# STM32.net
KiCad netlist of a schematic drawn in Altium Designer
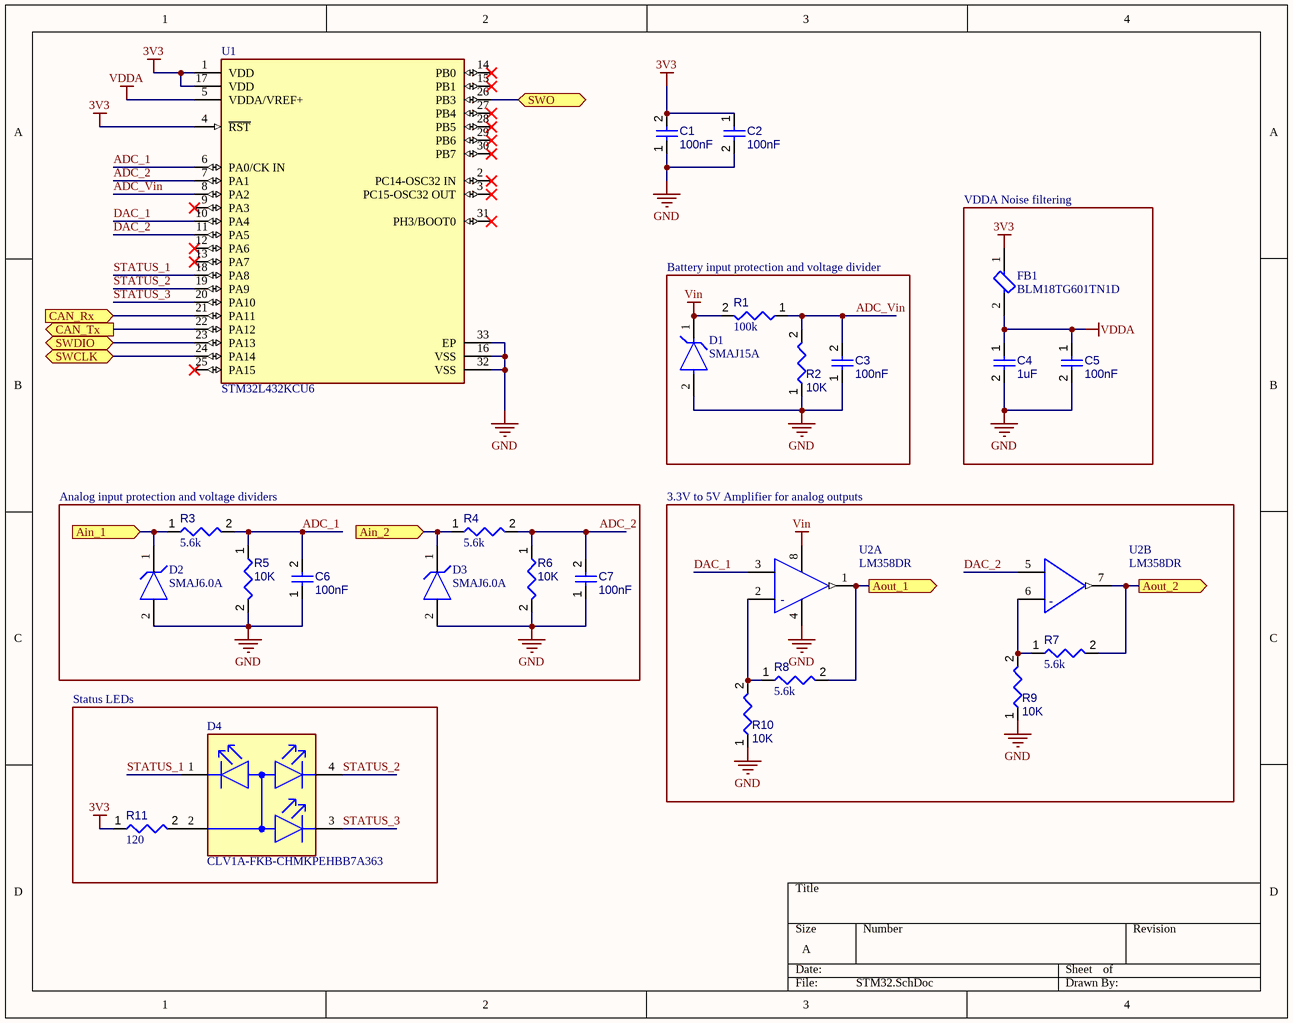
[diagram p0: STM32.SchDoc]

(export (version "E")
  (design (tool "Eeschema 10.0.6"))
  (components
    (comp (ref "C1")
      (value "100nF")
      (footprint "CAPC0402(1005)60_L")
      (description "Chip Capacitor, 100nF +/-20%, 10V, 0402, Thickness 0.6 mm")
      (fields (field (name "TOLERANCE") "20%"))
      (libsource (lib "Bronco Racing") (part "CAP-NP-2"))
    )
    (comp (ref "C2")
      (value "100nF")
      (footprint "CAPC0402(1005)60_L")
      (description "Chip Capacitor, 100nF +/-20%, 10V, 0402, Thickness 0.6 mm")
      (fields (field (name "TOLERANCE") "20%"))
      (libsource (lib "Bronco Racing") (part "CAP-NP-2"))
    )
    (comp (ref "C3")
      (value "100nF")
      (footprint "CAPC0402(1005)60_L")
      (description "Chip Capacitor, 100nF +/-20%, 10V, 0402, Thickness 0.6 mm")
      (fields (field (name "TOLERANCE") "20%"))
      (libsource (lib "Bronco Racing") (part "CAP-NP-2"))
    )
    (comp (ref "C4")
      (value "1uF")
      (footprint "CAPC0402(1005)60_L")
      (description "Chip Capacitor, 1µF +/-20%, 10V, 0402, Thickness 0.6 mm")
      (fields (field (name "TOLERANCE") "10%"))
      (libsource (lib "Bronco Racing") (part "CAP-NP-2"))
    )
    (comp (ref "C5")
      (value "100nF")
      (footprint "CAPC0402(1005)60_L")
      (description "Chip Capacitor, 100nF +/-20%, 10V, 0402, Thickness 0.6 mm")
      (fields (field (name "TOLERANCE") "20%"))
      (libsource (lib "Bronco Racing") (part "CAP-NP-2"))
    )
    (comp (ref "C6")
      (value "100nF")
      (footprint "CAPC0402(1005)60_L")
      (description "Chip Capacitor, 100nF +/-20%, 10V, 0402, Thickness 0.6 mm")
      (fields (field (name "TOLERANCE") "20%"))
      (libsource (lib "Bronco Racing") (part "CAP-NP-2"))
    )
    (comp (ref "C7")
      (value "100nF")
      (footprint "CAPC0402(1005)60_L")
      (description "Chip Capacitor, 100nF +/-20%, 10V, 0402, Thickness 0.6 mm")
      (fields (field (name "TOLERANCE") "20%"))
      (libsource (lib "Bronco Racing") (part "CAP-NP-2"))
    )
    (comp (ref "D1")
      (value "SMAJ15A")
      (footprint "FP-SMA-MFG")
      (description "TVS DIODE 15V 24.4V SMA")
      (fields
        (field (name "OCTOPART") "https://octopart.com/smaj15a-bourns-12809353")
        (field (name "MANUFACTURER") "Bourns Inc.")
      )
      (libsource (lib "Altium Content Vault") (part "f813f71cba58e380607f5dd3caf9714"))
    )
    (comp (ref "D2")
      (value "SMAJ6.0A")
      (footprint "FP-SMA-MFG")
      (description "TVS DIODE 6V 10.3V SMA")
      (fields
        (field (name "OCTOPART") "https://octopart.com/smaj6.0a-bourns-12809397")
        (field (name "MANUFACTURER") "Bourns Inc.")
      )
      (libsource (lib "Altium Content Vault") (part "673ecd2ea4d7fb87b4005b0cb348b7d"))
    )
    (comp (ref "D3")
      (value "SMAJ6.0A")
      (footprint "FP-SMA-MFG")
      (description "TVS DIODE 6V 10.3V SMA")
      (fields
        (field (name "OCTOPART") "https://octopart.com/smaj6.0a-bourns-12809397")
        (field (name "MANUFACTURER") "Bourns Inc.")
      )
      (libsource (lib "Altium Content Vault") (part "673ecd2ea4d7fb87b4005b0cb348b7d"))
    )
    (comp (ref "D4")
      (value "CLV1A-FKB-CHMKPEHBB7A363")
      (footprint "FP-CLV1A-FKB-CHMKPEHBB7A3-MFG")
      (description "LED RGB 4PLCC SMD")
      (libsource (lib "Altium Content Vault") (part "37e83e7cb408f3cd33eae76522c4c17"))
    )
    (comp (ref "FB1")
      (value "BLM18TG601TN1D")
      (footprint "FP-BLM18-0_15-0_1-t0_6-MFG")
      (description "FERRITE BEAD 600 OHM 0603 1LN")
      (fields (field (name "TOLERANCE") "25%"))
      (libsource (lib "Altium Content Vault") (part "5f30dd21d616792df468990f7003faa"))
    )
    (comp (ref "R1")
      (value "100k")
      (footprint "RESC0402(1005)_L")
      (description "Chip Resistor, 100 kOhms, +/-1 %, 63 mW, -55 to 155 degC, 0402")
      (fields (field (name "POWER") "63mW") (field (name "TOLERANCE") "1%"))
      (libsource (lib "Bronco Racing") (part "RES-2"))
    )
    (comp (ref "R2")
      (value "10K")
      (footprint "RESC0402(1005)_L")
      (description "Chip Resistor, 10 kOhms, +/-1 %, 63 mW, -55 to 125 degC, 0402")
      (fields (field (name "POWER") "63mW") (field (name "TOLERANCE") "1%"))
      (libsource (lib "Bronco Racing") (part "RES-2"))
    )
    (comp (ref "R3")
      (value "5.6k")
      (footprint "RESC0402(1005)_L")
      (description "Chip Resistor, 5,6 kOhms, +/-5 %, 63 mW, -55 to 155 degC, 0402")
      (fields (field (name "TOLERANCE") "5%") (field (name "POWER") "63mW"))
      (libsource (lib "Bronco Racing") (part "RES-2"))
    )
    (comp (ref "R4")
      (value "5.6k")
      (footprint "RESC0402(1005)_L")
      (description "Chip Resistor, 5,6 kOhms, +/-5 %, 63 mW, -55 to 155 degC, 0402")
      (fields (field (name "TOLERANCE") "5%") (field (name "POWER") "63mW"))
      (libsource (lib "Bronco Racing") (part "RES-2"))
    )
    (comp (ref "R5")
      (value "10K")
      (footprint "RESC0402(1005)_L")
      (description "Chip Resistor, 10 kOhms, +/-1 %, 63 mW, -55 to 125 degC, 0402")
      (fields (field (name "POWER") "63mW") (field (name "TOLERANCE") "1%"))
      (libsource (lib "Bronco Racing") (part "RES-2"))
    )
    (comp (ref "R6")
      (value "10K")
      (footprint "RESC0402(1005)_L")
      (description "Chip Resistor, 10 kOhms, +/-1 %, 63 mW, -55 to 125 degC, 0402")
      (fields (field (name "POWER") "63mW") (field (name "TOLERANCE") "1%"))
      (libsource (lib "Bronco Racing") (part "RES-2"))
    )
    (comp (ref "R7")
      (value "5.6k")
      (footprint "RESC0402(1005)_L")
      (description "Chip Resistor, 5,6 kOhms, +/-5 %, 63 mW, -55 to 155 degC, 0402")
      (fields (field (name "TOLERANCE") "5%") (field (name "POWER") "63mW"))
      (libsource (lib "Bronco Racing") (part "RES-2"))
    )
    (comp (ref "R8")
      (value "5.6k")
      (footprint "RESC0402(1005)_L")
      (description "Chip Resistor, 5,6 kOhms, +/-5 %, 63 mW, -55 to 155 degC, 0402")
      (fields (field (name "TOLERANCE") "5%") (field (name "POWER") "63mW"))
      (libsource (lib "Bronco Racing") (part "RES-2"))
    )
    (comp (ref "R9")
      (value "10K")
      (footprint "RESC0402(1005)_L")
      (description "Chip Resistor, 10 kOhms, +/-1 %, 63 mW, -55 to 125 degC, 0402")
      (fields (field (name "POWER") "63mW") (field (name "TOLERANCE") "1%"))
      (libsource (lib "Bronco Racing") (part "RES-2"))
    )
    (comp (ref "R10")
      (value "10K")
      (footprint "RESC0402(1005)_L")
      (description "Chip Resistor, 10 kOhms, +/-1 %, 63 mW, -55 to 125 degC, 0402")
      (fields (field (name "POWER") "63mW") (field (name "TOLERANCE") "1%"))
      (libsource (lib "Bronco Racing") (part "RES-2"))
    )
    (comp (ref "R11")
      (value "120")
      (footprint "RESC0603(1608)_L")
      (description "Chip Resistor, 120 Ohms, +/-5 %, 0.1 W, -55 to 155 degC, 0603")
      (fields (field (name "POWER") "100mW") (field (name "TOLERANCE") "5%"))
      (libsource (lib "Bronco Racing") (part "RES-2"))
    )
    (comp (ref "U1")
      (value "STM32L432KCU6")
      (footprint "FP-UFQFPN32-A0B8-MFG")
      (description "IC MCU 32BIT 256KB FLASH 32QFPN")
      (fields
        (field (name "OCTOPART") "https://octopart.com/stm32l432kcu6-stmicroelectronics-71093510")
        (field (name "MANUFACTURER") "STMicroelectronics")
      )
      (libsource (lib "Altium Content Vault") (part "f3240dca552e0aa49c1b4baba198c12"))
    )
    (comp (ref "U2")
      (value "LM358DR")
      (footprint "FP-D0008A-MFG")
      (description "IC OPAMP GP 2 CIRCUIT 8SOIC")
      (libsource (lib "Altium Content Vault") (part "0afdfe5f461d2cdd85604ff8654be97"))
    )
  )
  (nets
    (net (code "1") (name "/ADC_1") (class "Default")
      (node (ref "C6") (pin "2") (pinfunction "2_2") (pintype "passive"))
      (node (ref "R3") (pin "2") (pinfunction "2_2") (pintype "passive"))
      (node (ref "R5") (pin "1") (pinfunction "1_1") (pintype "passive"))
      (node (ref "U1") (pin "6") (pinfunction "PA0/CK_IN_6") (pintype "bidirectional"))
    )
    (net (code "2") (name "/ADC_2") (class "Default")
      (node (ref "C7") (pin "2") (pinfunction "2_2") (pintype "passive"))
      (node (ref "R4") (pin "2") (pinfunction "2_2") (pintype "passive"))
      (node (ref "R6") (pin "1") (pinfunction "1_1") (pintype "passive"))
      (node (ref "U1") (pin "7") (pinfunction "PA1_7") (pintype "bidirectional"))
    )
    (net (code "3") (name "/ADC_Vin") (class "Default")
      (node (ref "C3") (pin "2") (pinfunction "2_2") (pintype "passive"))
      (node (ref "R1") (pin "1") (pinfunction "1_1") (pintype "passive"))
      (node (ref "R2") (pin "2") (pinfunction "2_2") (pintype "passive"))
      (node (ref "U1") (pin "8") (pinfunction "PA2_8") (pintype "bidirectional"))
    )
    (net (code "4") (name "/Ain_1") (class "Default")
      (node (ref "D2") (pin "1") (pinfunction "C_1") (pintype "passive"))
      (node (ref "R3") (pin "1") (pinfunction "1_1") (pintype "passive"))
    )
    (net (code "5") (name "/Ain_2") (class "Default")
      (node (ref "D3") (pin "1") (pinfunction "C_1") (pintype "passive"))
      (node (ref "R4") (pin "1") (pinfunction "1_1") (pintype "passive"))
    )
    (net (code "6") (name "/Aout_1") (class "Default")
      (node (ref "R8") (pin "2") (pinfunction "2_2") (pintype "passive"))
      (node (ref "U2") (pin "1") (pinfunction "1OUT_1") (pintype "output"))
    )
    (net (code "7") (name "/Aout_2") (class "Default")
      (node (ref "R7") (pin "2") (pinfunction "2_2") (pintype "passive"))
      (node (ref "U2") (pin "7") (pinfunction "2OUT_7") (pintype "output"))
    )
    (net (code "8") (name "/CAN_Rx") (class "Default")
      (node (ref "U1") (pin "21") (pinfunction "PA11_21") (pintype "bidirectional"))
    )
    (net (code "9") (name "/CAN_Tx") (class "Default")
      (node (ref "U1") (pin "22") (pinfunction "PA12_22") (pintype "bidirectional"))
    )
    (net (code "10") (name "/DAC_1") (class "Default")
      (node (ref "U1") (pin "10") (pinfunction "PA4_10") (pintype "bidirectional"))
      (node (ref "U2") (pin "3") (pinfunction "IN1+_3") (pintype "tri_state"))
    )
    (net (code "11") (name "/DAC_2") (class "Default")
      (node (ref "U1") (pin "11") (pinfunction "PA5_11") (pintype "bidirectional"))
      (node (ref "U2") (pin "5") (pinfunction "IN2+_5") (pintype "tri_state"))
    )
    (net (code "12") (name "/STATUS_1") (class "Default")
      (node (ref "D4") (pin "1") (pinfunction "RED(C)_1") (pintype "passive"))
      (node (ref "U1") (pin "18") (pinfunction "PA8_18") (pintype "bidirectional"))
    )
    (net (code "13") (name "/STATUS_2") (class "Default")
      (node (ref "D4") (pin "4") (pinfunction "GREEN(C)_4") (pintype "passive"))
      (node (ref "U1") (pin "19") (pinfunction "PA9_19") (pintype "bidirectional"))
    )
    (net (code "14") (name "/STATUS_3") (class "Default")
      (node (ref "D4") (pin "3") (pinfunction "BLUE(C)_3") (pintype "passive"))
      (node (ref "U1") (pin "20") (pinfunction "PA10_20") (pintype "bidirectional"))
    )
    (net (code "15") (name "/SWCLK") (class "Default")
      (node (ref "U1") (pin "24") (pinfunction "PA14_24") (pintype "bidirectional"))
    )
    (net (code "16") (name "/SWDIO") (class "Default")
      (node (ref "U1") (pin "23") (pinfunction "PA13_23") (pintype "bidirectional"))
    )
    (net (code "17") (name "/SWO") (class "Default")
      (node (ref "U1") (pin "26") (pinfunction "PB3_26") (pintype "bidirectional"))
    )
    (net (code "18") (name "3V3") (class "Default")
      (node (ref "C1") (pin "2") (pinfunction "2_2") (pintype "passive"))
      (node (ref "C2") (pin "1") (pinfunction "1_1") (pintype "passive"))
      (node (ref "FB1") (pin "1") (pinfunction "1_1") (pintype "passive"))
      (node (ref "R11") (pin "1") (pinfunction "1_1") (pintype "passive"))
      (node (ref "U1") (pin "1") (pinfunction "VDD_1") (pintype "power_in"))
      (node (ref "U1") (pin "17") (pinfunction "VDD_17") (pintype "power_in"))
      (node (ref "U1") (pin "4") (pinfunction "~{RST}_4") (pintype "input"))
    )
    (net (code "19") (name "GND") (class "Default")
      (node (ref "C1") (pin "1") (pinfunction "1_1") (pintype "passive"))
      (node (ref "C2") (pin "2") (pinfunction "2_2") (pintype "passive"))
      (node (ref "C3") (pin "1") (pinfunction "1_1") (pintype "passive"))
      (node (ref "C4") (pin "2") (pinfunction "2_2") (pintype "passive"))
      (node (ref "C5") (pin "2") (pinfunction "2_2") (pintype "passive"))
      (node (ref "C6") (pin "1") (pinfunction "1_1") (pintype "passive"))
      (node (ref "C7") (pin "1") (pinfunction "1_1") (pintype "passive"))
      (node (ref "D1") (pin "2") (pinfunction "A_2") (pintype "passive"))
      (node (ref "D2") (pin "2") (pinfunction "A_2") (pintype "passive"))
      (node (ref "D3") (pin "2") (pinfunction "A_2") (pintype "passive"))
      (node (ref "R10") (pin "1") (pinfunction "1_1") (pintype "passive"))
      (node (ref "R2") (pin "1") (pinfunction "1_1") (pintype "passive"))
      (node (ref "R5") (pin "2") (pinfunction "2_2") (pintype "passive"))
      (node (ref "R6") (pin "2") (pinfunction "2_2") (pintype "passive"))
      (node (ref "R9") (pin "1") (pinfunction "1_1") (pintype "passive"))
      (node (ref "U1") (pin "16") (pinfunction "VSS_16") (pintype "power_in"))
      (node (ref "U1") (pin "32") (pinfunction "VSS_32") (pintype "power_in"))
      (node (ref "U1") (pin "33") (pinfunction "EP_33") (pintype "power_in"))
      (node (ref "U2") (pin "4") (pinfunction "V-_4") (pintype "power_in"))
    )
    (net (code "20") (name "Net-(D4-COMMON_ANODE)") (class "Default")
      (node (ref "D4") (pin "2") (pinfunction "COMMON_ANODE_2") (pintype "passive"))
      (node (ref "R11") (pin "2") (pinfunction "2_2") (pintype "passive"))
    )
    (net (code "21") (name "Net-(U2A-IN1-)") (class "Default")
      (node (ref "R10") (pin "2") (pinfunction "2_2") (pintype "passive"))
      (node (ref "R8") (pin "1") (pinfunction "1_1") (pintype "passive"))
      (node (ref "U2") (pin "2") (pinfunction "IN1-_2") (pintype "tri_state"))
    )
    (net (code "22") (name "Net-(U2B-IN2-)") (class "Default")
      (node (ref "R7") (pin "1") (pinfunction "1_1") (pintype "passive"))
      (node (ref "R9") (pin "2") (pinfunction "2_2") (pintype "passive"))
      (node (ref "U2") (pin "6") (pinfunction "IN2-_6") (pintype "tri_state"))
    )
    (net (code "23") (name "VDDA") (class "Default")
      (node (ref "C4") (pin "1") (pinfunction "1_1") (pintype "passive"))
      (node (ref "C5") (pin "1") (pinfunction "1_1") (pintype "passive"))
      (node (ref "FB1") (pin "2") (pinfunction "2_2") (pintype "passive"))
      (node (ref "U1") (pin "5") (pinfunction "VDDA/VREF+_5") (pintype "power_in"))
    )
    (net (code "24") (name "Vin") (class "Default")
      (node (ref "D1") (pin "1") (pinfunction "C_1") (pintype "passive"))
      (node (ref "R1") (pin "2") (pinfunction "2_2") (pintype "passive"))
      (node (ref "U2") (pin "8") (pinfunction "V+_8") (pintype "power_in"))
    )
    (net (code "25") (name "unconnected-(U1-PA3-Pad9)") (class "Default")
      (node (ref "U1") (pin "9") (pinfunction "PA3_9") (pintype "bidirectional+no_connect"))
    )
    (net (code "26") (name "unconnected-(U1-PA6-Pad12)") (class "Default")
      (node (ref "U1") (pin "12") (pinfunction "PA6_12") (pintype "bidirectional+no_connect"))
    )
    (net (code "27") (name "unconnected-(U1-PA7-Pad13)") (class "Default")
      (node (ref "U1") (pin "13") (pinfunction "PA7_13") (pintype "bidirectional+no_connect"))
    )
    (net (code "28") (name "unconnected-(U1-PA15-Pad25)") (class "Default")
      (node (ref "U1") (pin "25") (pinfunction "PA15_25") (pintype "bidirectional+no_connect"))
    )
    (net (code "29") (name "unconnected-(U1-PB0-Pad14)") (class "Default")
      (node (ref "U1") (pin "14") (pinfunction "PB0_14") (pintype "bidirectional+no_connect"))
    )
    (net (code "30") (name "unconnected-(U1-PB1-Pad15)") (class "Default")
      (node (ref "U1") (pin "15") (pinfunction "PB1_15") (pintype "bidirectional+no_connect"))
    )
    (net (code "31") (name "unconnected-(U1-PB4-Pad27)") (class "Default")
      (node (ref "U1") (pin "27") (pinfunction "PB4_27") (pintype "bidirectional+no_connect"))
    )
    (net (code "32") (name "unconnected-(U1-PB5-Pad28)") (class "Default")
      (node (ref "U1") (pin "28") (pinfunction "PB5_28") (pintype "bidirectional+no_connect"))
    )
    (net (code "33") (name "unconnected-(U1-PB6-Pad29)") (class "Default")
      (node (ref "U1") (pin "29") (pinfunction "PB6_29") (pintype "bidirectional+no_connect"))
    )
    (net (code "34") (name "unconnected-(U1-PB7-Pad30)") (class "Default")
      (node (ref "U1") (pin "30") (pinfunction "PB7_30") (pintype "bidirectional+no_connect"))
    )
    (net (code "35") (name "unconnected-(U1-PC14-OSC32_IN-Pad2)") (class "Default")
      (node (ref "U1") (pin "2") (pinfunction "PC14-OSC32_IN_2") (pintype "bidirectional+no_connect"))
    )
    (net (code "36") (name "unconnected-(U1-PC15-OSC32_OUT-Pad3)") (class "Default")
      (node (ref "U1") (pin "3") (pinfunction "PC15-OSC32_OUT_3") (pintype "bidirectional+no_connect"))
    )
    (net (code "37") (name "unconnected-(U1-PH3{slash}BOOT0-Pad31)") (class "Default")
      (node (ref "U1") (pin "31") (pinfunction "PH3/BOOT0_31") (pintype "bidirectional+no_connect"))
    )
  )
)
